# KEA.net
KiCad netlist of a schematic drawn in Altium Designer
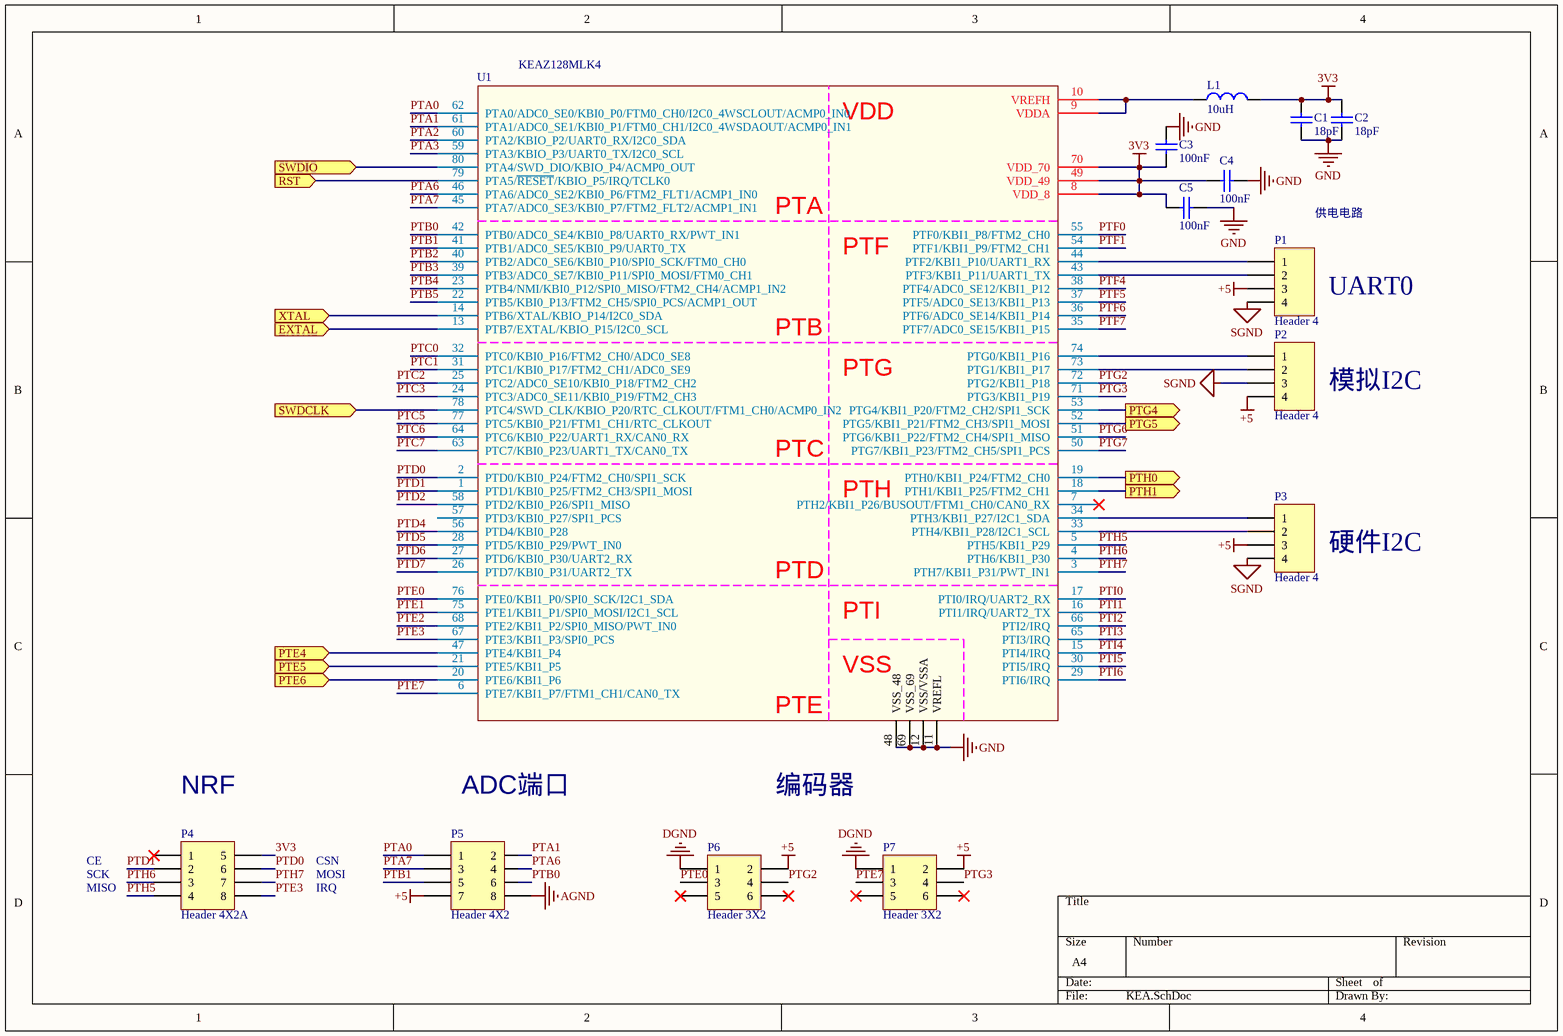
[diagram p0: KEA.SchDoc]

(export (version "E")
  (design (tool "Eeschema 10.0.6"))
  (components
    (comp (ref "C1")
      (value "18pF")
      (footprint "0603")
      (description "Capacitor")
      (libsource (lib "KEA128 Mini Core Board V1.0") (part "Cap"))
    )
    (comp (ref "C2")
      (value "18pF")
      (footprint "0603")
      (description "Capacitor")
      (libsource (lib "KEA128 Mini Core Board V1.0") (part "Cap"))
    )
    (comp (ref "C3")
      (value "100nF")
      (footprint "0603")
      (description "无极性电容")
      (fields (field (name "Comment") "Cap") (field (name "PUBLISHER") "Altium Limited"))
      (libsource (lib "haoze") (part "Cap"))
    )
    (comp (ref "C4")
      (value "100nF")
      (footprint "0603")
      (description "无极性电容")
      (fields (field (name "Comment") "Cap") (field (name "PUBLISHER") "Altium Limited"))
      (libsource (lib "haoze") (part "Cap"))
    )
    (comp (ref "C5")
      (value "100nF")
      (footprint "0603")
      (description "无极性电容")
      (fields (field (name "Comment") "Cap") (field (name "PUBLISHER") "Altium Limited"))
      (libsource (lib "haoze") (part "Cap"))
    )
    (comp (ref "L1")
      (value "10uH")
      (footprint "1206")
      (description "电感")
      (fields (field (name "Comment") "Inductor") (field (name "PUBLISHER") "Altium Limited"))
      (libsource (lib "SMT") (part "Inductor"))
    )
    (comp (ref "P1")
      (value "Header 4")
      (footprint "HDR1X4")
      (description "Header, 4-Pin")
      (fields (field (name "PUBLISHER") "Altium Limited"))
      (libsource (lib "Miscellaneous Connectors") (part "Header 4"))
    )
    (comp (ref "P2")
      (value "Header 4")
      (footprint "HDR1X4")
      (description "Header, 4-Pin")
      (fields (field (name "PUBLISHER") "Altium Limited"))
      (libsource (lib "Miscellaneous Connectors") (part "Header 4"))
    )
    (comp (ref "P3")
      (value "Header 4")
      (footprint "HDR1X4")
      (description "Header, 4-Pin")
      (fields (field (name "PUBLISHER") "Altium Limited"))
      (libsource (lib "Miscellaneous Connectors") (part "Header 4"))
    )
    (comp (ref "P4")
      (value "Header 4X2A")
      (footprint "HDR2X4_CEN")
      (description "Header, 4-Pin, Dual row")
      (fields (field (name "PUBLISHER") "Altium Limited"))
      (libsource (lib "Miscellaneous Connectors") (part "Header 4X2A"))
    )
    (comp (ref "P5")
      (value "Header 4X2")
      (footprint "HDR2X4")
      (description "Header, 4-Pin, Dual row")
      (fields (field (name "PUBLISHER") "Altium Limited"))
      (libsource (lib "Miscellaneous Connectors") (part "Header 4X2"))
    )
    (comp (ref "P6")
      (value "Header 3X2")
      (footprint "HDR2X3")
      (description "Header, 3-Pin, Dual row")
      (fields (field (name "PUBLISHER") "Altium Limited"))
      (libsource (lib "Miscellaneous Connectors") (part "Header 3X2"))
    )
    (comp (ref "P7")
      (value "Header 3X2")
      (footprint "HDR2X3")
      (description "Header, 3-Pin, Dual row")
      (fields (field (name "PUBLISHER") "Altium Limited"))
      (libsource (lib "Miscellaneous Connectors") (part "Header 3X2"))
    )
    (comp (ref "U1")
      (value "KEAZ128MLK4")
      (footprint "TQFP65P1650X1650X150-80N")
      (libsource (lib "KEA128 Mini Core Board V1.0") (part "SKEAZ128MLK4"))
    )
  )
  (nets
    (net (code "1") (name "+5") (class "Default")
      (node (ref "P1") (pin "3") (pinfunction "3_3") (pintype "passive"))
      (node (ref "P2") (pin "4") (pinfunction "4_4") (pintype "passive"))
      (node (ref "P3") (pin "3") (pinfunction "3_3") (pintype "passive"))
      (node (ref "P5") (pin "7") (pinfunction "7_7") (pintype "passive"))
      (node (ref "P6") (pin "2") (pinfunction "2_2") (pintype "passive"))
      (node (ref "P7") (pin "2") (pinfunction "2_2") (pintype "passive"))
    )
    (net (code "2") (name "/EXTAL") (class "Default")
      (node (ref "U1") (pin "13") (pinfunction "PTB7/EXTAL/KBIO_P15/I2C0_SCL_13") (pintype "passive"))
    )
    (net (code "3") (name "/PTA0") (class "Default")
      (node (ref "P5") (pin "1") (pinfunction "1_1") (pintype "passive"))
      (node (ref "U1") (pin "62") (pinfunction "PTA0/ADC0_SE0/KBI0_P0/FTM0_CH0/I2C0_4WSCLOUT/ACMP0_IN0_62") (pintype "passive"))
    )
    (net (code "4") (name "/PTA1") (class "Default")
      (node (ref "P5") (pin "2") (pinfunction "2_2") (pintype "passive"))
      (node (ref "U1") (pin "61") (pinfunction "PTA1/ADC0_SE1/KBI0_P1/FTM0_CH1/I2C0_4WSDAOUT/ACMP0_IN1_61") (pintype "passive"))
    )
    (net (code "5") (name "/PTA2") (class "Default")
      (node (ref "U1") (pin "60") (pinfunction "PTA2/KBIO_P2/UART0_RX/I2C0_SDA_60") (pintype "passive"))
    )
    (net (code "6") (name "/PTA3") (class "Default")
      (node (ref "U1") (pin "59") (pinfunction "PTA3/KBIO_P3/UART0_TX/I2C0_SCL_59") (pintype "passive"))
    )
    (net (code "7") (name "/PTA6") (class "Default")
      (node (ref "P5") (pin "4") (pinfunction "4_4") (pintype "passive"))
      (node (ref "U1") (pin "46") (pinfunction "PTA6/ADC0_SE2/KBI0_P6/FTM2_FLT1/ACMP1_IN0_46") (pintype "passive"))
    )
    (net (code "8") (name "/PTA7") (class "Default")
      (node (ref "P5") (pin "3") (pinfunction "3_3") (pintype "passive"))
      (node (ref "U1") (pin "45") (pinfunction "PTA7/ADC0_SE3/KBI0_P7/FTM2_FLT2/ACMP1_IN1_45") (pintype "passive"))
    )
    (net (code "9") (name "/PTB0") (class "Default")
      (node (ref "P5") (pin "6") (pinfunction "6_6") (pintype "passive"))
      (node (ref "U1") (pin "42") (pinfunction "PTB0/ADC0_SE4/KBI0_P8/UART0_RX/PWT_IN1_42") (pintype "passive"))
    )
    (net (code "10") (name "/PTB1") (class "Default")
      (node (ref "P5") (pin "5") (pinfunction "5_5") (pintype "passive"))
      (node (ref "U1") (pin "41") (pinfunction "PTB1/ADC0_SE5/KBI0_P9/UART0_TX_41") (pintype "passive"))
    )
    (net (code "11") (name "/PTB2") (class "Default")
      (node (ref "U1") (pin "40") (pinfunction "PTB2/ADC0_SE6/KBI0_P10/SPI0_SCK/FTM0_CH0_40") (pintype "passive"))
    )
    (net (code "12") (name "/PTB3") (class "Default")
      (node (ref "U1") (pin "39") (pinfunction "PTB3/ADC0_SE7/KBI0_P11/SPI0_MOSI/FTM0_CH1_39") (pintype "passive"))
    )
    (net (code "13") (name "/PTB4") (class "Default")
      (node (ref "U1") (pin "23") (pinfunction "PTB4/NMI/KBI0_P12/SPI0_MISO/FTM2_CH4/ACMP1_IN2_23") (pintype "passive"))
    )
    (net (code "14") (name "/PTB5") (class "Default")
      (node (ref "U1") (pin "22") (pinfunction "PTB5/KBI0_P13/FTM2_CH5/SPI0_PCS/ACMP1_OUT_22") (pintype "passive"))
    )
    (net (code "15") (name "/PTC0") (class "Default")
      (node (ref "U1") (pin "32") (pinfunction "PTC0/KBI0_P16/FTM2_CH0/ADC0_SE8_32") (pintype "passive"))
    )
    (net (code "16") (name "/PTC1") (class "Default")
      (node (ref "U1") (pin "31") (pinfunction "PTC1/KBI0_P17/FTM2_CH1/ADC0_SE9_31") (pintype "passive"))
    )
    (net (code "17") (name "/PTC2") (class "Default")
      (node (ref "U1") (pin "25") (pinfunction "PTC2/ADC0_SE10/KBI0_P18/FTM2_CH2_25") (pintype "passive"))
    )
    (net (code "18") (name "/PTC3") (class "Default")
      (node (ref "U1") (pin "24") (pinfunction "PTC3/ADC0_SE11/KBI0_P19/FTM2_CH3_24") (pintype "passive"))
    )
    (net (code "19") (name "/PTC5") (class "Default")
      (node (ref "U1") (pin "77") (pinfunction "PTC5/KBI0_P21/FTM1_CH1/RTC_CLKOUT_77") (pintype "passive"))
    )
    (net (code "20") (name "/PTC6") (class "Default")
      (node (ref "U1") (pin "64") (pinfunction "PTC6/KBI0_P22/UART1_RX/CAN0_RX_64") (pintype "passive"))
    )
    (net (code "21") (name "/PTC7") (class "Default")
      (node (ref "U1") (pin "63") (pinfunction "PTC7/KBI0_P23/UART1_TX/CAN0_TX_63") (pintype "passive"))
    )
    (net (code "22") (name "/PTD0") (class "Default")
      (node (ref "P4") (pin "6") (pinfunction "6_6") (pintype "passive"))
      (node (ref "U1") (pin "2") (pinfunction "PTD0/KBI0_P24/FTM2_CH0/SPI1_SCK_2") (pintype "passive"))
    )
    (net (code "23") (name "/PTD1") (class "Default")
      (node (ref "P4") (pin "2") (pinfunction "2_2") (pintype "passive"))
      (node (ref "U1") (pin "1") (pinfunction "PTD1/KBI0_P25/FTM2_CH3/SPI1_MOSI_1") (pintype "passive"))
    )
    (net (code "24") (name "/PTD2") (class "Default")
      (node (ref "U1") (pin "58") (pinfunction "PTD2/KBI0_P26/SPI1_MISO_58") (pintype "passive"))
    )
    (net (code "25") (name "/PTD4") (class "Default")
      (node (ref "U1") (pin "56") (pinfunction "PTD4/KBI0_P28_56") (pintype "passive"))
    )
    (net (code "26") (name "/PTD5") (class "Default")
      (node (ref "U1") (pin "28") (pinfunction "PTD5/KBI0_P29/PWT_IN0_28") (pintype "passive"))
    )
    (net (code "27") (name "/PTD6") (class "Default")
      (node (ref "U1") (pin "27") (pinfunction "PTD6/KBI0_P30/UART2_RX_27") (pintype "passive"))
    )
    (net (code "28") (name "/PTD7") (class "Default")
      (node (ref "U1") (pin "26") (pinfunction "PTD7/KBI0_P31/UART2_TX_26") (pintype "passive"))
    )
    (net (code "29") (name "/PTE0") (class "Default")
      (node (ref "P6") (pin "3") (pinfunction "3_3") (pintype "passive"))
      (node (ref "U1") (pin "76") (pinfunction "PTE0/KBI1_P0/SPI0_SCK/I2C1_SDA_76") (pintype "passive"))
    )
    (net (code "30") (name "/PTE1") (class "Default")
      (node (ref "U1") (pin "75") (pinfunction "PTE1/KBI1_P1/SPI0_MOSI/I2C1_SCL_75") (pintype "passive"))
    )
    (net (code "31") (name "/PTE2") (class "Default")
      (node (ref "U1") (pin "68") (pinfunction "PTE2/KBI1_P2/SPI0_MISO/PWT_IN0_68") (pintype "passive"))
    )
    (net (code "32") (name "/PTE3") (class "Default")
      (node (ref "P4") (pin "8") (pinfunction "8_8") (pintype "passive"))
      (node (ref "U1") (pin "67") (pinfunction "PTE3/KBI1_P3/SPI0_PCS_67") (pintype "passive"))
    )
    (net (code "33") (name "/PTE4") (class "Default")
      (node (ref "U1") (pin "47") (pinfunction "PTE4/KBI1_P4_47") (pintype "passive"))
    )
    (net (code "34") (name "/PTE5") (class "Default")
      (node (ref "U1") (pin "21") (pinfunction "PTE5/KBI1_P5_21") (pintype "passive"))
    )
    (net (code "35") (name "/PTE6") (class "Default")
      (node (ref "U1") (pin "20") (pinfunction "PTE6/KBI1_P6_20") (pintype "passive"))
    )
    (net (code "36") (name "/PTE7") (class "Default")
      (node (ref "P7") (pin "3") (pinfunction "3_3") (pintype "passive"))
      (node (ref "U1") (pin "6") (pinfunction "PTE7/KBI1_P7/FTM1_CH1/CAN0_TX_6") (pintype "passive"))
    )
    (net (code "37") (name "/PTF0") (class "Default")
      (node (ref "U1") (pin "55") (pinfunction "PTF0/KBI1_P8/FTM2_CH0_55") (pintype "passive"))
    )
    (net (code "38") (name "/PTF1") (class "Default")
      (node (ref "U1") (pin "54") (pinfunction "PTF1/KBI1_P9/FTM2_CH1_54") (pintype "passive"))
    )
    (net (code "39") (name "/PTF4") (class "Default")
      (node (ref "U1") (pin "38") (pinfunction "PTF4/ADC0_SE12/KBI1_P12_38") (pintype "passive"))
    )
    (net (code "40") (name "/PTF5") (class "Default")
      (node (ref "U1") (pin "37") (pinfunction "PTF5/ADC0_SE13/KBI1_P13_37") (pintype "passive"))
    )
    (net (code "41") (name "/PTF6") (class "Default")
      (node (ref "U1") (pin "36") (pinfunction "PTF6/ADC0_SE14/KBI1_P14_36") (pintype "passive"))
    )
    (net (code "42") (name "/PTF7") (class "Default")
      (node (ref "U1") (pin "35") (pinfunction "PTF7/ADC0_SE15/KBI1_P15_35") (pintype "passive"))
    )
    (net (code "43") (name "/PTG2") (class "Default")
      (node (ref "P6") (pin "4") (pinfunction "4_4") (pintype "passive"))
      (node (ref "U1") (pin "72") (pinfunction "PTG2/KBI1_P18_72") (pintype "passive"))
    )
    (net (code "44") (name "/PTG3") (class "Default")
      (node (ref "P7") (pin "4") (pinfunction "4_4") (pintype "passive"))
      (node (ref "U1") (pin "71") (pinfunction "PTG3/KBI1_P19_71") (pintype "passive"))
    )
    (net (code "45") (name "/PTG4") (class "Default")
      (node (ref "U1") (pin "53") (pinfunction "PTG4/KBI1_P20/FTM2_CH2/SPI1_SCK_53") (pintype "passive"))
    )
    (net (code "46") (name "/PTG5") (class "Default")
      (node (ref "U1") (pin "52") (pinfunction "PTG5/KBI1_P21/FTM2_CH3/SPI1_MOSI_52") (pintype "passive"))
    )
    (net (code "47") (name "/PTG6") (class "Default")
      (node (ref "U1") (pin "51") (pinfunction "PTG6/KBI1_P22/FTM2_CH4/SPI1_MISO_51") (pintype "passive"))
    )
    (net (code "48") (name "/PTG7") (class "Default")
      (node (ref "U1") (pin "50") (pinfunction "PTG7/KBI1_P23/FTM2_CH5/SPI1_PCS_50") (pintype "passive"))
    )
    (net (code "49") (name "/PTH0") (class "Default")
      (node (ref "U1") (pin "19") (pinfunction "PTH0/KBI1_P24/FTM2_CH0_19") (pintype "passive"))
    )
    (net (code "50") (name "/PTH1") (class "Default")
      (node (ref "U1") (pin "18") (pinfunction "PTH1/KBI1_P25/FTM2_CH1_18") (pintype "passive"))
    )
    (net (code "51") (name "/PTH5") (class "Default")
      (node (ref "P4") (pin "4") (pinfunction "4_4") (pintype "passive"))
      (node (ref "U1") (pin "5") (pinfunction "PTH5/KBI1_P29_5") (pintype "passive"))
    )
    (net (code "52") (name "/PTH6") (class "Default")
      (node (ref "P4") (pin "3") (pinfunction "3_3") (pintype "passive"))
      (node (ref "U1") (pin "4") (pinfunction "PTH6/KBI1_P30_4") (pintype "passive"))
    )
    (net (code "53") (name "/PTH7") (class "Default")
      (node (ref "P4") (pin "7") (pinfunction "7_7") (pintype "passive"))
      (node (ref "U1") (pin "3") (pinfunction "PTH7/KBI1_P31/PWT_IN1_3") (pintype "passive"))
    )
    (net (code "54") (name "/PTI0") (class "Default")
      (node (ref "U1") (pin "17") (pinfunction "PTI0/IRQ/UART2_RX_17") (pintype "passive"))
    )
    (net (code "55") (name "/PTI1") (class "Default")
      (node (ref "U1") (pin "16") (pinfunction "PTI1/IRQ/UART2_TX_16") (pintype "passive"))
    )
    (net (code "56") (name "/PTI2") (class "Default")
      (node (ref "U1") (pin "66") (pinfunction "PTI2/IRQ_66") (pintype "passive"))
    )
    (net (code "57") (name "/PTI3") (class "Default")
      (node (ref "U1") (pin "65") (pinfunction "PTI3/IRQ_65") (pintype "passive"))
    )
    (net (code "58") (name "/PTI4") (class "Default")
      (node (ref "U1") (pin "15") (pinfunction "PTI4/IRQ_15") (pintype "passive"))
    )
    (net (code "59") (name "/PTI5") (class "Default")
      (node (ref "U1") (pin "30") (pinfunction "PTI5/IRQ_30") (pintype "passive"))
    )
    (net (code "60") (name "/PTI6") (class "Default")
      (node (ref "U1") (pin "29") (pinfunction "PTI6/IRQ_29") (pintype "passive"))
    )
    (net (code "61") (name "/RST") (class "Default")
      (node (ref "U1") (pin "79") (pinfunction "PTA5/~{RESET}/KBIO_P5/IRQ/TCLK0_79") (pintype "passive"))
    )
    (net (code "62") (name "/SWDCLK") (class "Default")
      (node (ref "U1") (pin "78") (pinfunction "PTC4/SWD_CLK/KBIO_P20/RTC_CLKOUT/FTM1_CH0/ACMP0_IN2_78") (pintype "passive"))
    )
    (net (code "63") (name "/SWDIO") (class "Default")
      (node (ref "U1") (pin "80") (pinfunction "PTA4/SWD_DIO/KBIO_P4/ACMP0_OUT_80") (pintype "passive"))
    )
    (net (code "64") (name "/XTAL") (class "Default")
      (node (ref "U1") (pin "14") (pinfunction "PTB6/XTAL/KBIO_P14/I2C0_SDA_14") (pintype "passive"))
    )
    (net (code "65") (name "3V3") (class "Default")
      (node (ref "C1") (pin "1") (pinfunction "1_1") (pintype "passive"))
      (node (ref "C2") (pin "1") (pinfunction "1_1") (pintype "passive"))
      (node (ref "C3") (pin "1") (pinfunction "1_1") (pintype "passive"))
      (node (ref "C4") (pin "1") (pinfunction "1_1") (pintype "passive"))
      (node (ref "C5") (pin "1") (pinfunction "1_1") (pintype "passive"))
      (node (ref "L1") (pin "2") (pinfunction "2_2") (pintype "passive"))
      (node (ref "P4") (pin "5") (pinfunction "5_5") (pintype "passive"))
      (node (ref "U1") (pin "49") (pinfunction "VDD_49_49") (pintype "passive"))
      (node (ref "U1") (pin "70") (pinfunction "VDD_70_70") (pintype "passive"))
      (node (ref "U1") (pin "8") (pinfunction "VDD_8_8") (pintype "passive"))
    )
    (net (code "66") (name "AGND") (class "Default")
      (node (ref "P5") (pin "8") (pinfunction "8_8") (pintype "passive"))
    )
    (net (code "67") (name "DGND") (class "Default")
      (node (ref "P6") (pin "1") (pinfunction "1_1") (pintype "passive"))
      (node (ref "P7") (pin "1") (pinfunction "1_1") (pintype "passive"))
    )
    (net (code "68") (name "GND") (class "Default")
      (node (ref "C1") (pin "2") (pinfunction "2_2") (pintype "passive"))
      (node (ref "C2") (pin "2") (pinfunction "2_2") (pintype "passive"))
      (node (ref "C3") (pin "2") (pinfunction "2_2") (pintype "passive"))
      (node (ref "C4") (pin "2") (pinfunction "2_2") (pintype "passive"))
      (node (ref "C5") (pin "2") (pinfunction "2_2") (pintype "passive"))
      (node (ref "U1") (pin "11") (pinfunction "VREFL_11") (pintype "passive"))
      (node (ref "U1") (pin "12") (pinfunction "VSS/VSSA_12") (pintype "passive"))
      (node (ref "U1") (pin "48") (pinfunction "VSS_48_48") (pintype "passive"))
      (node (ref "U1") (pin "69") (pinfunction "VSS_69_69") (pintype "passive"))
    )
    (net (code "69") (name "Net-(U1-PTF2{slash}KBI1_P10{slash}UART1_RX)") (class "Default")
      (node (ref "P1") (pin "1") (pinfunction "1_1") (pintype "passive"))
      (node (ref "U1") (pin "44") (pinfunction "PTF2/KBI1_P10/UART1_RX_44") (pintype "passive"))
    )
    (net (code "70") (name "Net-(U1-PTF3{slash}KBI1_P11{slash}UART1_TX)") (class "Default")
      (node (ref "P1") (pin "2") (pinfunction "2_2") (pintype "passive"))
      (node (ref "U1") (pin "43") (pinfunction "PTF3/KBI1_P11/UART1_TX_43") (pintype "passive"))
    )
    (net (code "71") (name "Net-(U1-PTG0{slash}KBI1_P16)") (class "Default")
      (node (ref "P2") (pin "1") (pinfunction "1_1") (pintype "passive"))
      (node (ref "U1") (pin "74") (pinfunction "PTG0/KBI1_P16_74") (pintype "passive"))
    )
    (net (code "72") (name "Net-(U1-PTG1{slash}KBI1_P17)") (class "Default")
      (node (ref "P2") (pin "2") (pinfunction "2_2") (pintype "passive"))
      (node (ref "U1") (pin "73") (pinfunction "PTG1/KBI1_P17_73") (pintype "passive"))
    )
    (net (code "73") (name "Net-(U1-PTH3{slash}KBI1_P27{slash}I2C1_SDA)") (class "Default")
      (node (ref "P3") (pin "1") (pinfunction "1_1") (pintype "passive"))
      (node (ref "U1") (pin "34") (pinfunction "PTH3/KBI1_P27/I2C1_SDA_34") (pintype "passive"))
    )
    (net (code "74") (name "Net-(U1-PTH4{slash}KBI1_P28{slash}I2C1_SCL)") (class "Default")
      (node (ref "P3") (pin "2") (pinfunction "2_2") (pintype "passive"))
      (node (ref "U1") (pin "33") (pinfunction "PTH4/KBI1_P28/I2C1_SCL_33") (pintype "passive"))
    )
    (net (code "75") (name "Net-(U1-VDDA)") (class "Default")
      (node (ref "L1") (pin "1") (pinfunction "1_1") (pintype "passive"))
      (node (ref "U1") (pin "10") (pinfunction "VREFH_10") (pintype "passive"))
      (node (ref "U1") (pin "9") (pinfunction "VDDA_9") (pintype "passive"))
    )
    (net (code "76") (name "SGND") (class "Default")
      (node (ref "P1") (pin "4") (pinfunction "4_4") (pintype "passive"))
      (node (ref "P2") (pin "3") (pinfunction "3_3") (pintype "passive"))
      (node (ref "P3") (pin "4") (pinfunction "4_4") (pintype "passive"))
    )
    (net (code "77") (name "unconnected-(P4-Pad1)") (class "Default")
      (node (ref "P4") (pin "1") (pinfunction "1_1") (pintype "passive+no_connect"))
    )
    (net (code "78") (name "unconnected-(P6-Pad5)") (class "Default")
      (node (ref "P6") (pin "5") (pinfunction "5_5") (pintype "passive+no_connect"))
    )
    (net (code "79") (name "unconnected-(P6-Pad6)") (class "Default")
      (node (ref "P6") (pin "6") (pinfunction "6_6") (pintype "passive+no_connect"))
    )
    (net (code "80") (name "unconnected-(P7-Pad5)") (class "Default")
      (node (ref "P7") (pin "5") (pinfunction "5_5") (pintype "passive+no_connect"))
    )
    (net (code "81") (name "unconnected-(P7-Pad6)") (class "Default")
      (node (ref "P7") (pin "6") (pinfunction "6_6") (pintype "passive+no_connect"))
    )
    (net (code "82") (name "unconnected-(U1-PTD3{slash}KBI0_P27{slash}SPI1_PCS-Pad57)") (class "Default")
      (node (ref "U1") (pin "57") (pinfunction "PTD3/KBI0_P27/SPI1_PCS_57") (pintype "passive"))
    )
    (net (code "83") (name "unconnected-(U1-PTH2{slash}KBI1_P26{slash}BUSOUT{slash}FTM1_CH0{slash}CAN0_RX-Pad7)") (class "Default")
      (node (ref "U1") (pin "7") (pinfunction "PTH2/KBI1_P26/BUSOUT/FTM1_CH0/CAN0_RX_7") (pintype "passive+no_connect"))
    )
  )
)
